# One_Shot.net
KiCad netlist of a schematic drawn in Altium Designer
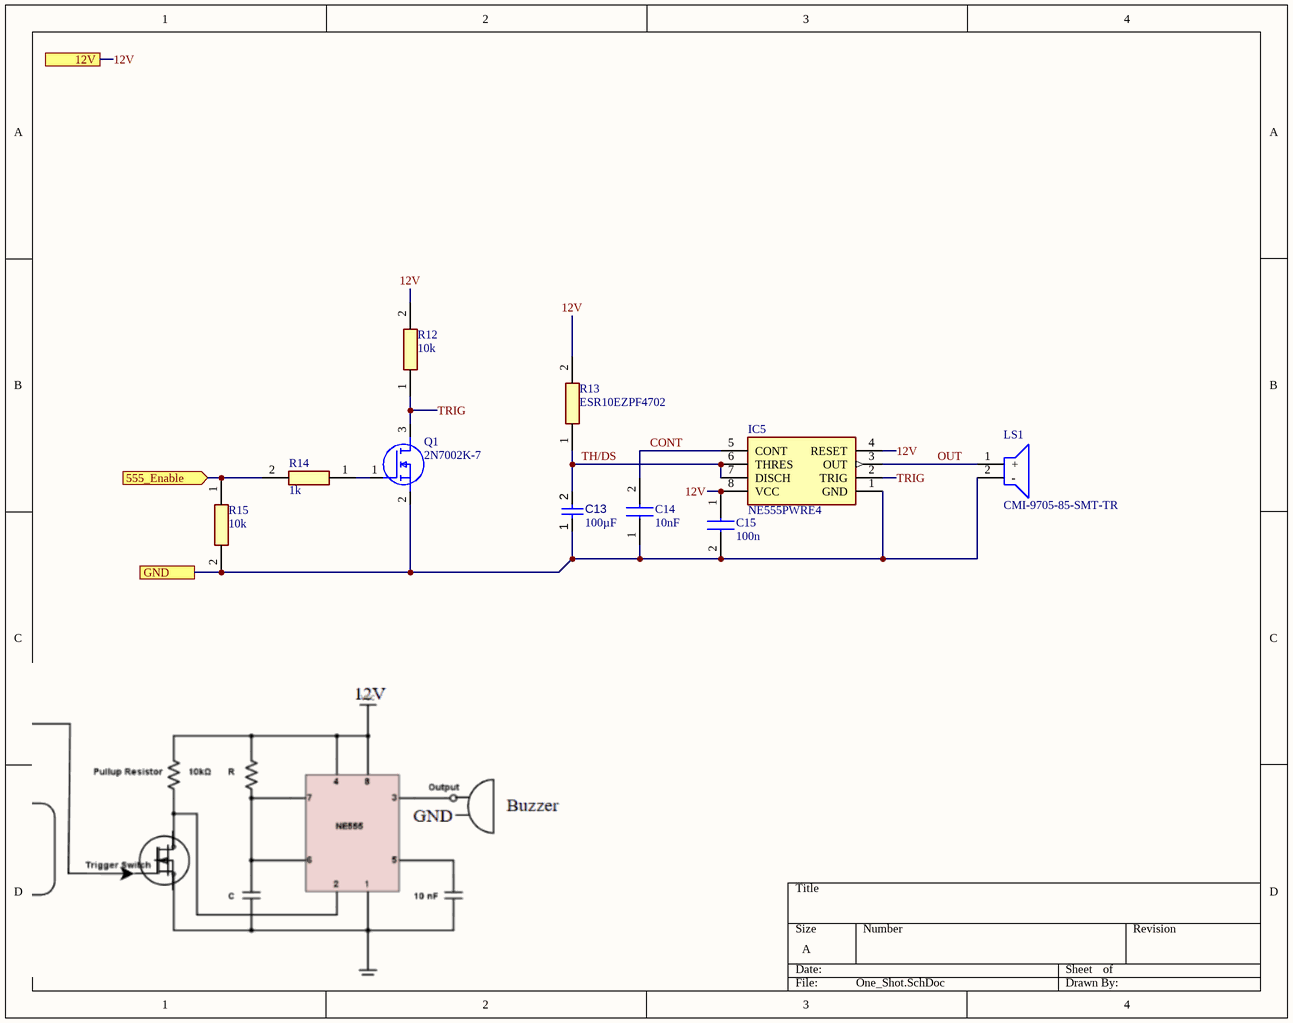
[diagram p0: One_Shot.SchDoc]

(export (version "E")
  (design (tool "Eeschema 10.0.6"))
  (components
    (comp (ref "C13")
      (value "100µF")
      (footprint "CAPC0805(2012)145_L")
      (description "Chip Capacitor, 100µF +/-20%, 6.3V, 0805, Thickness 1.45 mm")
      (fields (field (name "TOLERANCE") "10%") (field (name "Comment") "Capacitor 100µF +/-20% 6.3V 0805"))
      (libsource (lib "Hector Dela Rosa") (part "CAP-NP-2"))
    )
    (comp (ref "C14")
      (value "10nF")
      (footprint "SamacSys:C0805")
      (description "Capacitor")
      (fields
        (field (name "MANUFACTURER_PART_NUMBER") "C0805C103F1GACAUTO")
        (field (name "MOUSER PART NUMBER") "80-C0805C103F1GAUTO")
      )
      (libsource (lib "SamacSys") (part "C0805C103F1GACAUTO"))
    )
    (comp (ref "C15")
      (value "100n")
      (footprint "SamacSys:CAPC2012X147N")
      (description "Capacitor")
      (fields
        (field (name "MANUFACTURER_PART_NUMBER") "KGF21BR71H104KT")
        (field (name "MOUSER PART NUMBER") "581-KGF21BR71H104KT")
      )
      (libsource (lib "SamacSys") (part "KGF21BR71H104KT"))
    )
    (comp (ref "IC5")
      (value "NE555PWRE4")
      (footprint "SamacSys:SOP65P640X120-8N")
      (description "Integrated Circuit")
      (fields (field (name "MOUSER PART NUMBER") "595-NE555PWRE4"))
      (libsource (lib "SamacSys") (part "NE555PWRE4"))
    )
    (comp (ref "LS1")
      (value "CMI-9705-85-SMT-TR")
      (footprint "SamacSys:CMI970585SMTTR")
      (description "Loudspeaker or Buzzer")
      (fields (field (name "MOUSER PART NUMBER") "490-CMI-9705-85SMTTR"))
      (libsource (lib "SamacSys") (part "CMI-9705-85-SMT-TR"))
    )
    (comp (ref "Q1")
      (value "2N7002K-7")
      (footprint "SamacSys:SOT96P240X115-3N")
      (description "N-CHANNEL ENHANCEMENT MODE MOSFET")
      (fields (field (name "MOUSER PART NUMBER") "621-2N7002K-7"))
      (libsource (lib "SamacSys") (part "2N7002K-7"))
    )
    (comp (ref "R12")
      (value "10k")
      (footprint "SamacSys:RESC2012X60N")
      (description "Resistor")
      (fields (field (name "MANUFACTURER_PART_NUMBER") "RV0805JR-0710KL"))
      (libsource (lib "SamacSys") (part "RV0805JR-0710KL"))
    )
    (comp (ref "R13")
      (value "ESR10EZPF4702")
      (footprint "SamacSys:RESC2012X65N")
      (description "Resistor")
      (fields (field (name "MOUSER PART NUMBER") "755-ESR10EZPF4702"))
      (libsource (lib "SamacSys") (part "ESR10EZPF4702"))
    )
    (comp (ref "R14")
      (value "1k")
      (footprint "RESC2013X65N")
      (description "Resistor")
      (fields
        (field (name "MANUFACTURER_PART_NUMBER") "WCR0805LF1001FPLT")
        (field (name "MOUSER PART NUMBER") "66-WCR0805LF1001FPLT")
      )
      (libsource (lib "SamacSys") (part "WCR0805LF1001FPLT"))
    )
    (comp (ref "R15")
      (value "10k")
      (footprint "SamacSys:RESC2012X60N")
      (description "Resistor")
      (fields (field (name "MANUFACTURER_PART_NUMBER") "RV0805JR-0710KL"))
      (libsource (lib "") (part "RV0805JR-0710KL_1"))
    )
  )
  (nets
    (net (code "1") (name "/12V") (class "Default")
      (node (ref "C15") (pin "1") (pinfunction "1_1") (pintype "passive"))
      (node (ref "IC5") (pin "4") (pinfunction "RESET_4") (pintype "passive"))
      (node (ref "IC5") (pin "8") (pinfunction "VCC_8") (pintype "power_in"))
      (node (ref "R12") (pin "2") (pinfunction "2_2") (pintype "passive"))
      (node (ref "R13") (pin "2") (pinfunction "2_2") (pintype "passive"))
    )
    (net (code "2") (name "/555_Enable") (class "Default")
      (node (ref "R14") (pin "2") (pinfunction "2_2") (pintype "passive"))
      (node (ref "R15") (pin "1") (pinfunction "1_1") (pintype "passive"))
    )
    (net (code "3") (name "/CONT") (class "Default")
      (node (ref "C14") (pin "2") (pinfunction "2_2") (pintype "passive"))
      (node (ref "IC5") (pin "5") (pinfunction "CONT_5") (pintype "passive"))
    )
    (net (code "4") (name "/GND") (class "Default")
      (node (ref "C13") (pin "1") (pinfunction "1_1") (pintype "passive"))
      (node (ref "C14") (pin "1") (pinfunction "1_1") (pintype "passive"))
      (node (ref "C15") (pin "2") (pinfunction "2_2") (pintype "passive"))
      (node (ref "IC5") (pin "1") (pinfunction "GND_1") (pintype "power_in"))
      (node (ref "LS1") (pin "2") (pinfunction "-_2") (pintype "passive"))
      (node (ref "Q1") (pin "2") (pinfunction "S_2") (pintype "passive"))
      (node (ref "R15") (pin "2") (pinfunction "2_2") (pintype "passive"))
    )
    (net (code "5") (name "/OUT") (class "Default")
      (node (ref "IC5") (pin "3") (pinfunction "OUT_3") (pintype "output"))
      (node (ref "LS1") (pin "1") (pinfunction "+_1") (pintype "passive"))
    )
    (net (code "6") (name "/TH{slash}DS") (class "Default")
      (node (ref "C13") (pin "2") (pinfunction "2_2") (pintype "passive"))
      (node (ref "IC5") (pin "6") (pinfunction "THRES_6") (pintype "passive"))
      (node (ref "IC5") (pin "7") (pinfunction "DISCH_7") (pintype "passive"))
      (node (ref "R13") (pin "1") (pinfunction "1_1") (pintype "passive"))
    )
    (net (code "7") (name "/TRIG") (class "Default")
      (node (ref "IC5") (pin "2") (pinfunction "TRIG_2") (pintype "passive"))
      (node (ref "Q1") (pin "3") (pinfunction "D_3") (pintype "passive"))
      (node (ref "R12") (pin "1") (pinfunction "1_1") (pintype "passive"))
    )
    (net (code "8") (name "Net-(Q1-G)") (class "Default")
      (node (ref "Q1") (pin "1") (pinfunction "G_1") (pintype "passive"))
      (node (ref "R14") (pin "1") (pinfunction "1_1") (pintype "passive"))
    )
  )
)
